# Reprogrammation.net
KiCad netlist of a schematic drawn in Altium Designer
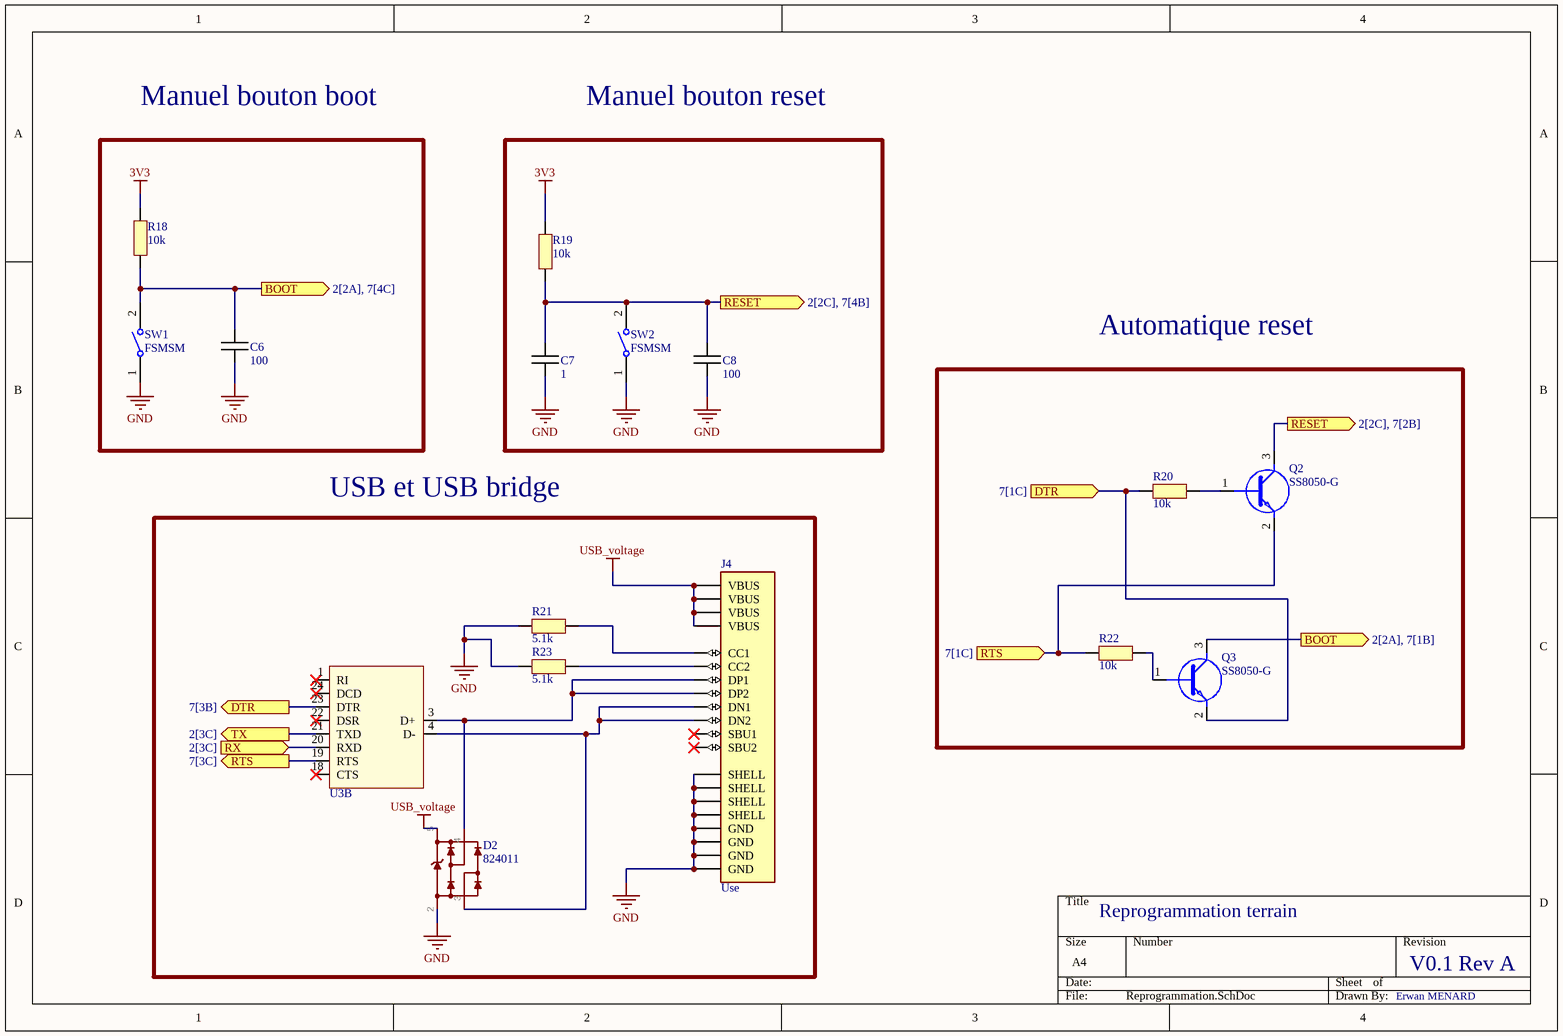
[diagram p0: Reprogrammation.SchDoc]

(export (version "E")
  (design (tool "Eeschema 10.0.6"))
  (components
    (comp (ref "C6")
      (value "100")
      (footprint "CAPC1005X06N")
      (libsource (lib "SCHLibrary") (part "Capacitor"))
    )
    (comp (ref "C7") (value "1") (footprint "CAPC1005X06N") (libsource (lib "SCHLibrary") (part "Capacitor")))
    (comp (ref "C8")
      (value "100")
      (footprint "CAPC1005X06N")
      (libsource (lib "SCHLibrary") (part "Capacitor"))
    )
    (comp (ref "D2") (value "824011") (footprint "824011") (libsource (lib "SCHLibrary") (part "824011")))
    (comp (ref "J4")
      (value "Use")
      (footprint "USB4085-GF-A")
      (description "Connecteurs USB USB Type C, 2.0, Rec, TH , G/F, RA , Top Mnt, T & R")
      (libsource (lib "SCHLibrary") (part "USB4085-GF-A"))
    )
    (comp (ref "Q2")
      (value "SS8050-G")
      (footprint "SS8050-G")
      (description "Bipolar Transistors - BJT NPN TRANSISTOR 1.5A 40V")
      (libsource (lib "SCHLibrary") (part "SS8050-G"))
    )
    (comp (ref "Q3")
      (value "SS8050-G")
      (footprint "SS8050-G")
      (description "Bipolar Transistors - BJT NPN TRANSISTOR 1.5A 40V")
      (libsource (lib "SCHLibrary") (part "SS8050-G"))
    )
    (comp (ref "R18") (value "10k") (footprint "RESC1005X06N") (libsource (lib "") (part "Resistor_1")))
    (comp (ref "R19") (value "10k") (footprint "RESC1005X06N") (libsource (lib "") (part "Resistor_1")))
    (comp (ref "R20")
      (value "10k")
      (footprint "RESC1005X06N")
      (libsource (lib "SCHLibrary") (part "Resistor"))
    )
    (comp (ref "R21") (value "5.1k") (footprint "RESC1005X06N") (libsource (lib "") (part "Resistor_2")))
    (comp (ref "R22")
      (value "10k")
      (footprint "RESC1005X06N")
      (libsource (lib "SCHLibrary") (part "Resistor"))
    )
    (comp (ref "R23") (value "5.1k") (footprint "RESC1005X06N") (libsource (lib "") (part "Resistor_2")))
    (comp (ref "SW1")
      (value "FSMSM")
      (footprint "TECO-FSMSM-2_V")
      (description "FSMSM Push Button Switch, 50 mA, -35 to 85 degC, 2-Pin SMD, RoHS, Bulk")
      (fields (field (name "MANUFACTURER") "TE Connectivity"))
      (libsource (lib "SCHLibrary") (part "CMP-2000-07511-1"))
    )
    (comp (ref "SW2")
      (value "FSMSM")
      (footprint "TECO-FSMSM-2_V")
      (description "FSMSM Push Button Switch, 50 mA, -35 to 85 degC, 2-Pin SMD, RoHS, Bulk")
      (fields (field (name "MANUFACTURER") "TE Connectivity"))
      (libsource (lib "SCHLibrary") (part "CMP-2000-07511-1"))
    )
    (comp (ref "U3")
      (value "CP2104-F03-GM")
      (footprint "PQFN50P400X400X80_HS-25N")
      (description "USB Bridge, USB to UART USB 2.0 UART Interface 24-QFN (4x4)")
      (libsource (lib "SCHLibrary") (part "USBBridge"))
    )
  )
  (nets
    (net (code "1") (name "/BOOT") (class "Default")
      (node (ref "C6") (pin "1") (pinfunction "1_1") (pintype "passive"))
      (node (ref "Q3") (pin "3") (pinfunction "C_3") (pintype "passive"))
      (node (ref "R18") (pin "1") (pinfunction "1_1") (pintype "passive"))
      (node (ref "SW1") (pin "2") (pinfunction "2_2") (pintype "passive"))
    )
    (net (code "2") (name "/DTR") (class "Default")
      (node (ref "Q3") (pin "2") (pinfunction "E_2") (pintype "passive"))
      (node (ref "R20") (pin "2") (pinfunction "2_2") (pintype "passive"))
      (node (ref "U3") (pin "23") (pinfunction "DTR_23") (pintype "passive"))
    )
    (net (code "3") (name "/RESET") (class "Default")
      (node (ref "C7") (pin "1") (pinfunction "1_1") (pintype "passive"))
      (node (ref "C8") (pin "1") (pinfunction "1_1") (pintype "passive"))
      (node (ref "Q2") (pin "3") (pinfunction "C_3") (pintype "passive"))
      (node (ref "R19") (pin "1") (pinfunction "1_1") (pintype "passive"))
      (node (ref "SW2") (pin "2") (pinfunction "2_2") (pintype "passive"))
    )
    (net (code "4") (name "/RTS") (class "Default")
      (node (ref "Q2") (pin "2") (pinfunction "E_2") (pintype "passive"))
      (node (ref "R22") (pin "2") (pinfunction "2_2") (pintype "passive"))
      (node (ref "U3") (pin "19") (pinfunction "RTS_19") (pintype "passive"))
    )
    (net (code "5") (name "/RX") (class "Default")
      (node (ref "U3") (pin "20") (pinfunction "RXD_20") (pintype "passive"))
    )
    (net (code "6") (name "/TX") (class "Default")
      (node (ref "U3") (pin "21") (pinfunction "TXD_21") (pintype "passive"))
    )
    (net (code "7") (name "3V3") (class "Default")
      (node (ref "R18") (pin "2") (pinfunction "2_2") (pintype "passive"))
      (node (ref "R19") (pin "2") (pinfunction "2_2") (pintype "passive"))
    )
    (net (code "8") (name "GND") (class "Default")
      (node (ref "C6") (pin "2") (pinfunction "2_2") (pintype "passive"))
      (node (ref "C7") (pin "2") (pinfunction "2_2") (pintype "passive"))
      (node (ref "C8") (pin "2") (pinfunction "2_2") (pintype "passive"))
      (node (ref "D2") (pin "2") (pinfunction "GND_2") (pintype "power_in"))
      (node (ref "J4") (pin "A1") (pinfunction "GND_A1") (pintype "power_in"))
      (node (ref "J4") (pin "A12") (pinfunction "GND_A12") (pintype "power_in"))
      (node (ref "J4") (pin "B1") (pinfunction "GND_B1") (pintype "power_in"))
      (node (ref "J4") (pin "B12") (pinfunction "GND_B12") (pintype "power_in"))
      (node (ref "J4") (pin "S1") (pinfunction "SHELL_S1") (pintype "passive"))
      (node (ref "J4") (pin "S2") (pinfunction "SHELL_S2") (pintype "passive"))
      (node (ref "J4") (pin "S3") (pinfunction "SHELL_S3") (pintype "passive"))
      (node (ref "J4") (pin "S4") (pinfunction "SHELL_S4") (pintype "passive"))
      (node (ref "R21") (pin "1") (pinfunction "1_1") (pintype "passive"))
      (node (ref "R23") (pin "1") (pinfunction "1_1") (pintype "passive"))
      (node (ref "SW1") (pin "1") (pinfunction "1_1") (pintype "passive"))
      (node (ref "SW2") (pin "1") (pinfunction "1_1") (pintype "passive"))
    )
    (net (code "9") (name "Net-(D2-1)") (class "Default")
      (node (ref "D2") (pin "3") (pinfunction "1_3") (pintype "passive"))
      (node (ref "J4") (pin "A7") (pinfunction "DN1_A7") (pintype "bidirectional"))
      (node (ref "J4") (pin "B7") (pinfunction "DN2_B7") (pintype "bidirectional"))
      (node (ref "U3") (pin "4") (pinfunction "D-_4") (pintype "passive"))
    )
    (net (code "10") (name "Net-(D2-2)") (class "Default")
      (node (ref "D2") (pin "4") (pinfunction "2_4") (pintype "passive"))
      (node (ref "J4") (pin "A6") (pinfunction "DP1_A6") (pintype "bidirectional"))
      (node (ref "J4") (pin "B6") (pinfunction "DP2_B6") (pintype "bidirectional"))
      (node (ref "U3") (pin "3") (pinfunction "D+_3") (pintype "passive"))
    )
    (net (code "11") (name "Net-(J4-CC1)") (class "Default")
      (node (ref "J4") (pin "A5") (pinfunction "CC1_A5") (pintype "bidirectional"))
      (node (ref "R21") (pin "2") (pinfunction "2_2") (pintype "passive"))
    )
    (net (code "12") (name "Net-(J4-CC2)") (class "Default")
      (node (ref "J4") (pin "B5") (pinfunction "CC2_B5") (pintype "bidirectional"))
      (node (ref "R23") (pin "2") (pinfunction "2_2") (pintype "passive"))
    )
    (net (code "13") (name "Net-(Q2-B)") (class "Default")
      (node (ref "Q2") (pin "1") (pinfunction "B_1") (pintype "passive"))
      (node (ref "R20") (pin "1") (pinfunction "1_1") (pintype "passive"))
    )
    (net (code "14") (name "Net-(Q3-B)") (class "Default")
      (node (ref "Q3") (pin "1") (pinfunction "B_1") (pintype "passive"))
      (node (ref "R22") (pin "1") (pinfunction "1_1") (pintype "passive"))
    )
    (net (code "15") (name "USB_voltage") (class "Default")
      (node (ref "D2") (pin "5") (pinfunction "VDD_5") (pintype "power_in"))
      (node (ref "J4") (pin "A4") (pinfunction "VBUS_A4") (pintype "power_in"))
      (node (ref "J4") (pin "A9") (pinfunction "VBUS_A9") (pintype "power_in"))
      (node (ref "J4") (pin "B4") (pinfunction "VBUS_B4") (pintype "power_in"))
      (node (ref "J4") (pin "B9") (pinfunction "VBUS_B9") (pintype "power_in"))
    )
    (net (code "16") (name "unconnected-(J4-SBU1-PadA8)") (class "Default")
      (node (ref "J4") (pin "A8") (pinfunction "SBU1_A8") (pintype "bidirectional+no_connect"))
    )
    (net (code "17") (name "unconnected-(J4-SBU2-PadB8)") (class "Default")
      (node (ref "J4") (pin "B8") (pinfunction "SBU2_B8") (pintype "bidirectional+no_connect"))
    )
    (net (code "18") (name "unconnected-(U3B-CTS-Pad18)") (class "Default")
      (node (ref "U3") (pin "18") (pinfunction "CTS_18") (pintype "passive+no_connect"))
    )
    (net (code "19") (name "unconnected-(U3B-DCD-Pad24)") (class "Default")
      (node (ref "U3") (pin "24") (pinfunction "DCD_24") (pintype "passive+no_connect"))
    )
    (net (code "20") (name "unconnected-(U3B-DSR-Pad22)") (class "Default")
      (node (ref "U3") (pin "22") (pinfunction "DSR_22") (pintype "passive+no_connect"))
    )
    (net (code "21") (name "unconnected-(U3B-RI-Pad1)") (class "Default")
      (node (ref "U3") (pin "1") (pinfunction "RI_1") (pintype "passive+no_connect"))
    )
  )
)
